# machin.net
KiCad netlist of a schematic drawn in Altium Designer
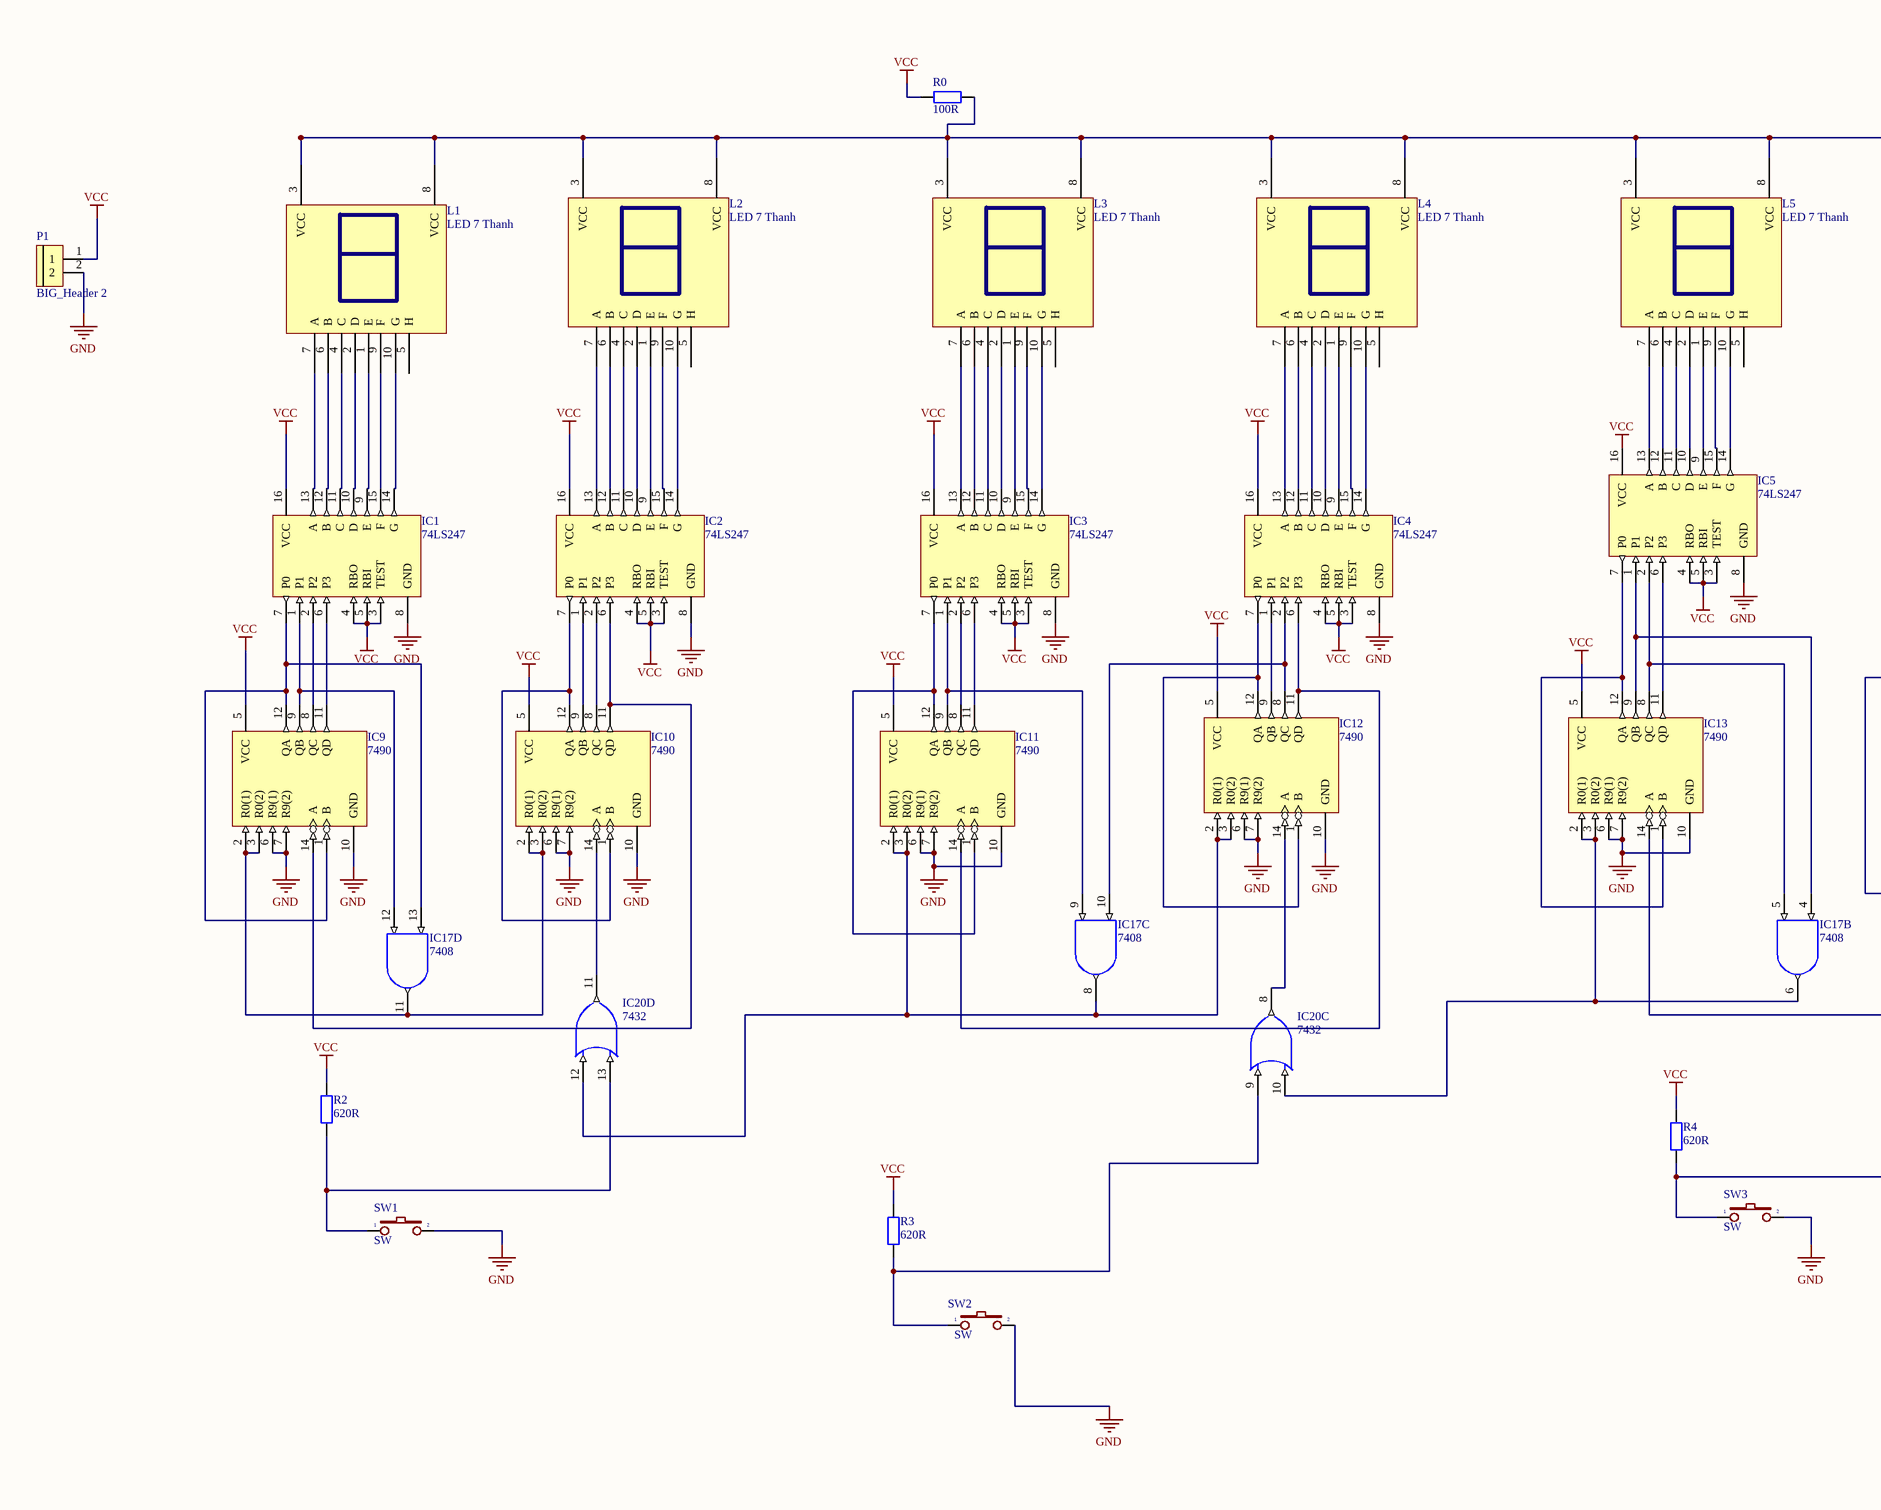
[diagram p0: machin.SchDoc, left]
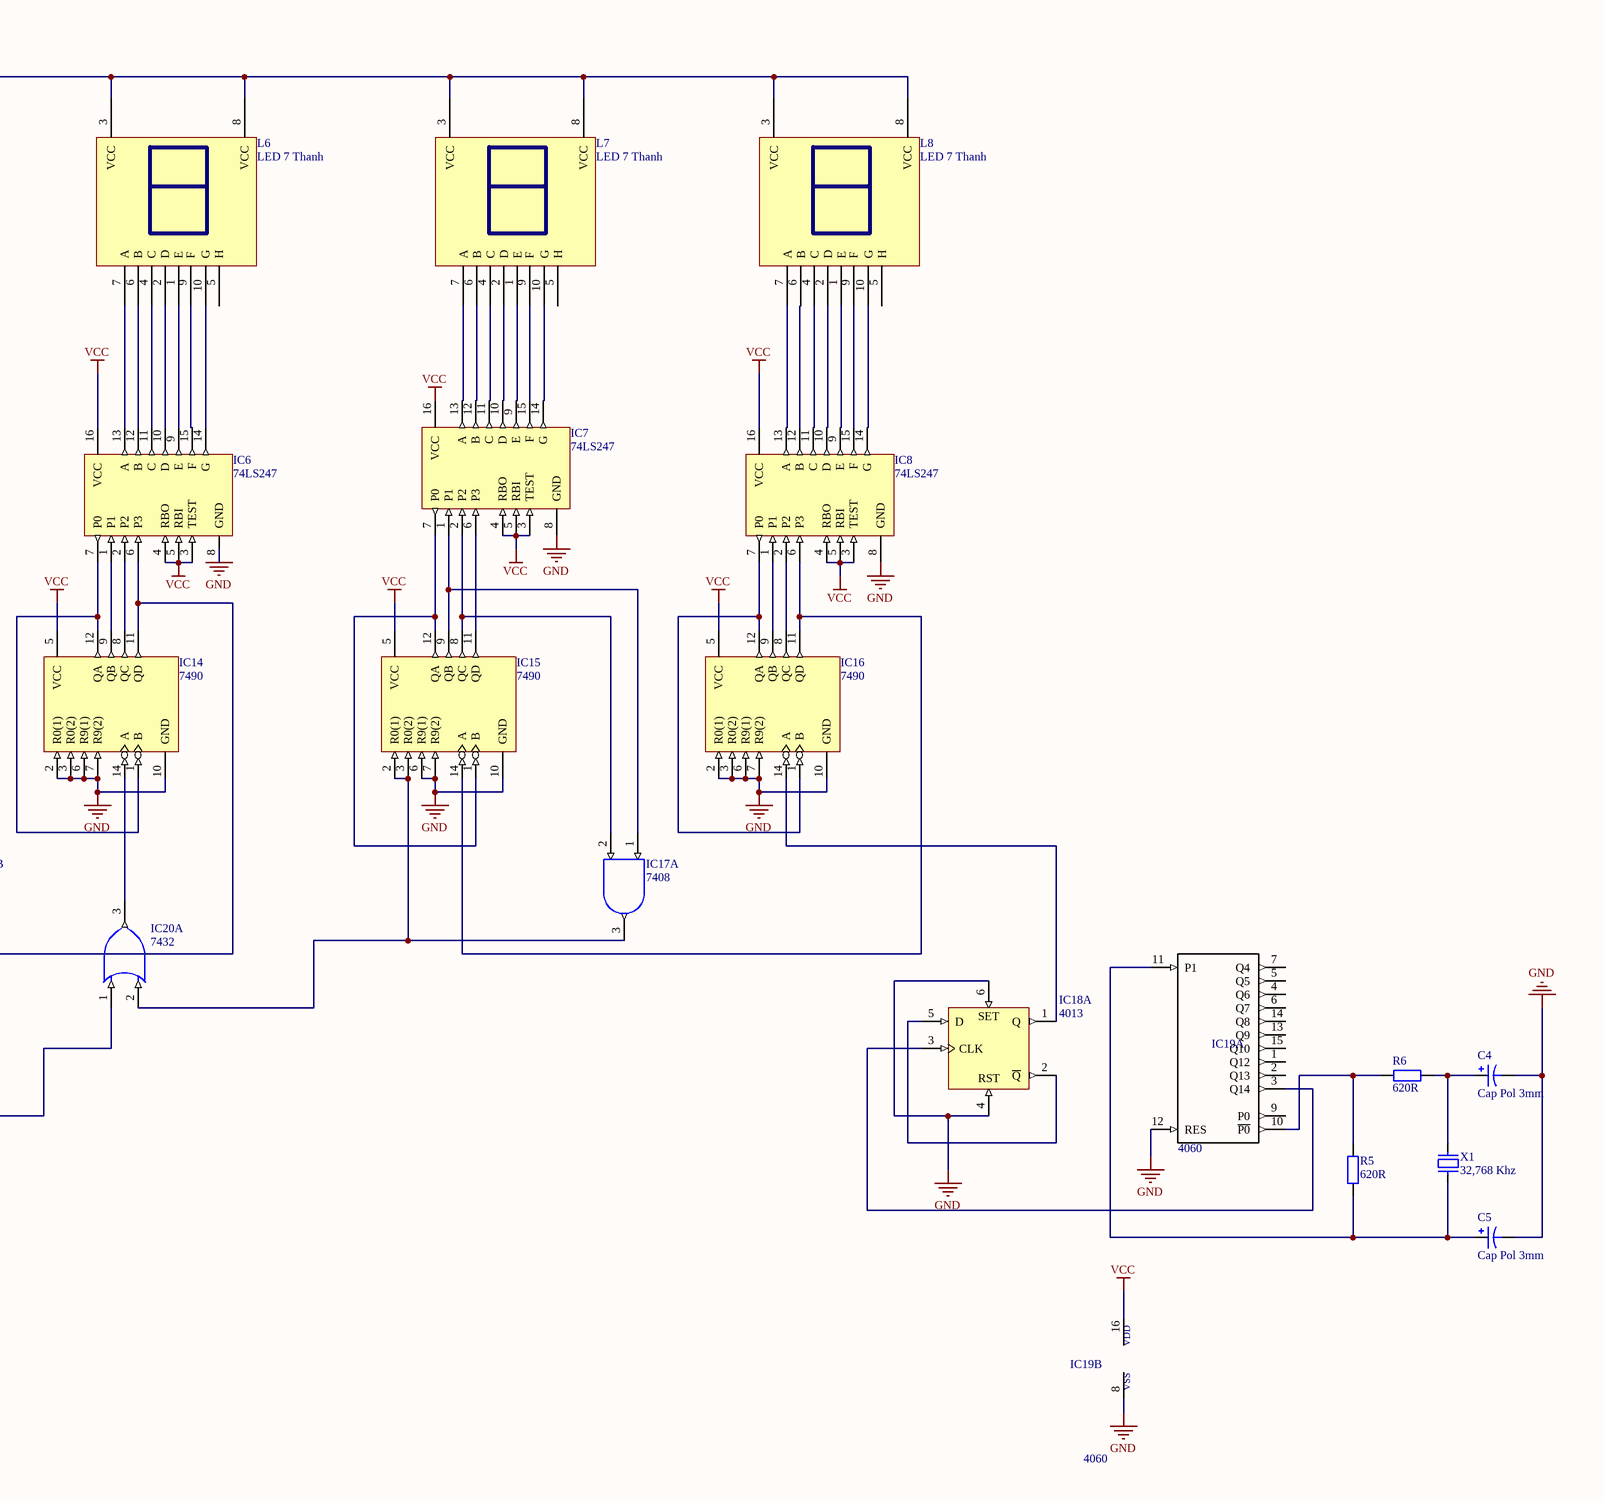
[diagram p1: machin.SchDoc, right]

(export (version "E")
  (design (tool "Eeschema 10.0.6"))
  (components
    (comp (ref "C4")
      (value "Cap Pol 3mm")
      (footprint "C3MM")
      (description "Polarized Capacitor (Axial)")
      (fields (field (name "PUBLISHER") "Altium Limited"))
      (libsource (lib "NBBLib 14-03-2012") (part "Cap Pol 3mm"))
    )
    (comp (ref "C5")
      (value "Cap Pol 3mm")
      (footprint "C3MM")
      (description "Polarized Capacitor (Axial)")
      (fields (field (name "PUBLISHER") "Altium Limited"))
      (libsource (lib "NBBLib 14-03-2012") (part "Cap Pol 3mm"))
    )
    (comp (ref "IC1")
      (value "74LS247")
      (footprint "DIP16")
      (fields (field (name "COPYRIGHT BY") "VanDungEvn@Gmail.com"))
      (libsource (lib "KhanhBK_SCH_Library_2") (part "74247"))
    )
    (comp (ref "IC2")
      (value "74LS247")
      (footprint "DIP16")
      (fields (field (name "COPYRIGHT BY") "VanDungEvn@Gmail.com"))
      (libsource (lib "KhanhBK_SCH_Library_2") (part "74247"))
    )
    (comp (ref "IC3")
      (value "74LS247")
      (footprint "DIP16")
      (fields (field (name "COPYRIGHT BY") "VanDungEvn@Gmail.com"))
      (libsource (lib "KhanhBK_SCH_Library_2") (part "74247"))
    )
    (comp (ref "IC4")
      (value "74LS247")
      (footprint "DIP16")
      (fields (field (name "COPYRIGHT BY") "VanDungEvn@Gmail.com"))
      (libsource (lib "KhanhBK_SCH_Library_2") (part "74247"))
    )
    (comp (ref "IC5")
      (value "74LS247")
      (footprint "DIP16")
      (fields (field (name "COPYRIGHT BY") "VanDungEvn@Gmail.com"))
      (libsource (lib "KhanhBK_SCH_Library_2") (part "74247"))
    )
    (comp (ref "IC6")
      (value "74LS247")
      (footprint "DIP16")
      (fields (field (name "COPYRIGHT BY") "VanDungEvn@Gmail.com"))
      (libsource (lib "KhanhBK_SCH_Library_2") (part "74247"))
    )
    (comp (ref "IC7")
      (value "74LS247")
      (footprint "DIP16")
      (fields (field (name "COPYRIGHT BY") "VanDungEvn@Gmail.com"))
      (libsource (lib "KhanhBK_SCH_Library_2") (part "74247"))
    )
    (comp (ref "IC8")
      (value "74LS247")
      (footprint "DIP16")
      (fields (field (name "COPYRIGHT BY") "VanDungEvn@Gmail.com"))
      (libsource (lib "KhanhBK_SCH_Library_2") (part "74247"))
    )
    (comp (ref "IC9")
      (value "7490")
      (footprint "DIP14/W0.3")
      (description "4-Bit Decade Counter")
      (libsource (lib "KhanhBK_SCH_Library_2") (part "7490"))
    )
    (comp (ref "IC10")
      (value "7490")
      (footprint "DIP14/W0.3")
      (description "4-Bit Decade Counter")
      (libsource (lib "KhanhBK_SCH_Library_2") (part "7490"))
    )
    (comp (ref "IC11")
      (value "7490")
      (footprint "DIP14/W0.3")
      (description "4-Bit Decade Counter")
      (libsource (lib "KhanhBK_SCH_Library_2") (part "7490"))
    )
    (comp (ref "IC12")
      (value "7490")
      (footprint "DIP14/W0.3")
      (description "4-Bit Decade Counter")
      (libsource (lib "KhanhBK_SCH_Library_2") (part "7490"))
    )
    (comp (ref "IC13")
      (value "7490")
      (footprint "DIP14/W0.3")
      (description "4-Bit Decade Counter")
      (libsource (lib "KhanhBK_SCH_Library_2") (part "7490"))
    )
    (comp (ref "IC14")
      (value "7490")
      (footprint "DIP14/W0.3")
      (description "4-Bit Decade Counter")
      (libsource (lib "KhanhBK_SCH_Library_2") (part "7490"))
    )
    (comp (ref "IC15")
      (value "7490")
      (footprint "DIP14/W0.3")
      (description "4-Bit Decade Counter")
      (libsource (lib "KhanhBK_SCH_Library_2") (part "7490"))
    )
    (comp (ref "IC16")
      (value "7490")
      (footprint "DIP14/W0.3")
      (description "4-Bit Decade Counter")
      (libsource (lib "KhanhBK_SCH_Library_2") (part "7490"))
    )
    (comp (ref "IC17")
      (value "7408")
      (footprint "DIP14/W0.3")
      (description "Quad 2-Input AND Gate")
      (libsource (lib "Library AL") (part "7408"))
    )
    (comp (ref "IC18")
      (value "4013")
      (footprint "DIP14")
      (description "Dual D-Type Flip-Flop")
      (fields (field (name "CREAT BY") "VanDungEvn@Gmail.com"))
      (libsource (lib "KhanhBK_SCH_Library_2") (part "4013"))
    )
    (comp (ref "IC19")
      (value "4060")
      (footprint "*DIL16")
      (description "Standoff; Round; Nylon; 6-32x3/8 Thread; 1/4 OD; 3/4 Length ¦ Abbatron / HH Smith 4060")
      (fields (field (name "MF") "Abbatron"))
      (libsource (lib "4060") (part "4060"))
    )
    (comp (ref "IC20")
      (value "7432")
      (footprint "DIP14/W0.3")
      (description "Quad 2-Input OR Gate")
      (libsource (lib "KhanhBK_SCH_Library_2") (part "7432"))
    )
    (comp (ref "L1")
      (value "LED 7 Thanh")
      (footprint "LED 7x1 0.56")
      (description "Dán")
      (libsource (lib "Led") (part "LED 7x1 0.56 Anot"))
    )
    (comp (ref "L2")
      (value "LED 7 Thanh")
      (footprint "LED 7x1 0.56")
      (description "Dán")
      (libsource (lib "Led") (part "LED 7x1 0.56 Anot"))
    )
    (comp (ref "L3")
      (value "LED 7 Thanh")
      (footprint "LED 7x1 0.56")
      (description "Dán")
      (libsource (lib "Led") (part "LED 7x1 0.56 Anot"))
    )
    (comp (ref "L4")
      (value "LED 7 Thanh")
      (footprint "LED 7x1 0.56")
      (description "Dán")
      (libsource (lib "Led") (part "LED 7x1 0.56 Anot"))
    )
    (comp (ref "L5")
      (value "LED 7 Thanh")
      (footprint "LED 7x1 0.56")
      (description "Dán")
      (libsource (lib "Led") (part "LED 7x1 0.56 Anot"))
    )
    (comp (ref "L6")
      (value "LED 7 Thanh")
      (footprint "LED 7x1 0.56")
      (description "Dán")
      (libsource (lib "Led") (part "LED 7x1 0.56 Anot"))
    )
    (comp (ref "L7")
      (value "LED 7 Thanh")
      (footprint "LED 7x1 0.56")
      (description "Dán")
      (libsource (lib "Led") (part "LED 7x1 0.56 Anot"))
    )
    (comp (ref "L8")
      (value "LED 7 Thanh")
      (footprint "LED 7x1 0.56")
      (description "Dán")
      (libsource (lib "Led") (part "LED 7x1 0.56 Anot"))
    )
    (comp (ref "P1")
      (value "BIG_Header 2")
      (footprint "BIG_Header 2")
      (libsource (lib "NBBLib 14-03-2012") (part "BIG_Header 2"))
    )
    (comp (ref "R0")
      (value "100R")
      (footprint "tro vach 1/2w")
      (description "Cắm")
      (libsource (lib "Resistor") (part "Tro Vach 1/2W 5% 100R"))
    )
    (comp (ref "R2")
      (value "620R")
      (footprint "tro vach 1/4w")
      (description "Cắm")
      (libsource (lib "Resistor") (part "Tro Vach 1/4W 5% 620R"))
    )
    (comp (ref "R3")
      (value "620R")
      (footprint "tro vach 1/4w")
      (description "Cắm")
      (libsource (lib "Resistor") (part "Tro Vach 1/4W 5% 620R"))
    )
    (comp (ref "R4")
      (value "620R")
      (footprint "tro vach 1/4w")
      (description "Cắm")
      (libsource (lib "Resistor") (part "Tro Vach 1/4W 5% 620R"))
    )
    (comp (ref "R5")
      (value "620R")
      (footprint "tro vach 1/4w")
      (description "Cắm")
      (libsource (lib "Resistor") (part "Tro Vach 1/4W 5% 620R"))
    )
    (comp (ref "R6")
      (value "620R")
      (footprint "tro vach 1/4w")
      (description "Cắm")
      (libsource (lib "Resistor") (part "Tro Vach 1/4W 5% 620R"))
    )
    (comp (ref "SW1")
      (value "SW")
      (footprint "SW2")
      (description "Switch button 2 pin")
      (libsource (lib "KhanhBK_SCH_Library_2") (part "SW2"))
    )
    (comp (ref "SW2")
      (value "SW")
      (footprint "SW2")
      (description "Switch button 2 pin")
      (libsource (lib "KhanhBK_SCH_Library_2") (part "SW2"))
    )
    (comp (ref "SW3")
      (value "SW")
      (footprint "SW2")
      (description "Switch button 2 pin")
      (libsource (lib "KhanhBK_SCH_Library_2") (part "SW2"))
    )
    (comp (ref "X1")
      (value "32,768 Khz")
      (footprint "XT32k")
      (description "Crystal 32,768kHz for timer real")
      (libsource (lib "KhanhBK_SCH_Library_2") (part "XT32k"))
    )
  )
  (nets
    (net (code "1") (name "GND") (class "Default")
      (node (ref "C4") (pin "2") (pinfunction "2_2") (pintype "passive"))
      (node (ref "C5") (pin "2") (pinfunction "2_2") (pintype "passive"))
      (node (ref "IC1") (pin "8") (pinfunction "GND_8") (pintype "power_in"))
      (node (ref "IC10") (pin "10") (pinfunction "GND_10") (pintype "power_in"))
      (node (ref "IC10") (pin "6") (pinfunction "R9(1)_6") (pintype "input"))
      (node (ref "IC10") (pin "7") (pinfunction "R9(2)_7") (pintype "input"))
      (node (ref "IC11") (pin "10") (pinfunction "GND_10") (pintype "power_in"))
      (node (ref "IC11") (pin "6") (pinfunction "R9(1)_6") (pintype "input"))
      (node (ref "IC11") (pin "7") (pinfunction "R9(2)_7") (pintype "input"))
      (node (ref "IC12") (pin "10") (pinfunction "GND_10") (pintype "power_in"))
      (node (ref "IC12") (pin "6") (pinfunction "R9(1)_6") (pintype "input"))
      (node (ref "IC12") (pin "7") (pinfunction "R9(2)_7") (pintype "input"))
      (node (ref "IC13") (pin "10") (pinfunction "GND_10") (pintype "power_in"))
      (node (ref "IC13") (pin "6") (pinfunction "R9(1)_6") (pintype "input"))
      (node (ref "IC13") (pin "7") (pinfunction "R9(2)_7") (pintype "input"))
      (node (ref "IC14") (pin "10") (pinfunction "GND_10") (pintype "power_in"))
      (node (ref "IC14") (pin "2") (pinfunction "R0(1)_2") (pintype "input"))
      (node (ref "IC14") (pin "3") (pinfunction "R0(2)_3") (pintype "input"))
      (node (ref "IC14") (pin "6") (pinfunction "R9(1)_6") (pintype "input"))
      (node (ref "IC14") (pin "7") (pinfunction "R9(2)_7") (pintype "input"))
      (node (ref "IC15") (pin "10") (pinfunction "GND_10") (pintype "power_in"))
      (node (ref "IC15") (pin "6") (pinfunction "R9(1)_6") (pintype "input"))
      (node (ref "IC15") (pin "7") (pinfunction "R9(2)_7") (pintype "input"))
      (node (ref "IC16") (pin "10") (pinfunction "GND_10") (pintype "power_in"))
      (node (ref "IC16") (pin "2") (pinfunction "R0(1)_2") (pintype "input"))
      (node (ref "IC16") (pin "3") (pinfunction "R0(2)_3") (pintype "input"))
      (node (ref "IC16") (pin "6") (pinfunction "R9(1)_6") (pintype "input"))
      (node (ref "IC16") (pin "7") (pinfunction "R9(2)_7") (pintype "input"))
      (node (ref "IC17") (pin "7") (pinfunction "GND_7") (pintype "power_in"))
      (node (ref "IC18") (pin "4") (pinfunction "RST_4") (pintype "input"))
      (node (ref "IC18") (pin "6") (pinfunction "S_6") (pintype "input"))
      (node (ref "IC18") (pin "7") (pinfunction "GND_7") (pintype "power_in"))
      (node (ref "IC19") (pin "12") (pinfunction "RES_12") (pintype "input"))
      (node (ref "IC19") (pin "8") (pinfunction "VSS_8") (pintype "power_in"))
      (node (ref "IC2") (pin "8") (pinfunction "GND_8") (pintype "power_in"))
      (node (ref "IC20") (pin "7") (pinfunction "GND_7") (pintype "power_in"))
      (node (ref "IC3") (pin "8") (pinfunction "GND_8") (pintype "power_in"))
      (node (ref "IC4") (pin "8") (pinfunction "GND_8") (pintype "power_in"))
      (node (ref "IC5") (pin "8") (pinfunction "GND_8") (pintype "power_in"))
      (node (ref "IC6") (pin "8") (pinfunction "GND_8") (pintype "power_in"))
      (node (ref "IC7") (pin "8") (pinfunction "GND_8") (pintype "power_in"))
      (node (ref "IC8") (pin "8") (pinfunction "GND_8") (pintype "power_in"))
      (node (ref "IC9") (pin "10") (pinfunction "GND_10") (pintype "power_in"))
      (node (ref "IC9") (pin "6") (pinfunction "R9(1)_6") (pintype "input"))
      (node (ref "IC9") (pin "7") (pinfunction "R9(2)_7") (pintype "input"))
      (node (ref "P1") (pin "2") (pinfunction "2_2") (pintype "passive"))
      (node (ref "SW1") (pin "2") (pinfunction "2_2") (pintype "passive"))
      (node (ref "SW2") (pin "2") (pinfunction "2_2") (pintype "passive"))
      (node (ref "SW3") (pin "2") (pinfunction "2_2") (pintype "passive"))
    )
    (net (code "2") (name "Net-(C4-Pad1)") (class "Default")
      (node (ref "C4") (pin "1") (pinfunction "1_1") (pintype "passive"))
      (node (ref "R6") (pin "1") (pinfunction "1_1") (pintype "passive"))
      (node (ref "X1") (pin "2") (pinfunction "2_2") (pintype "passive"))
    )
    (net (code "3") (name "Net-(IC1-A)") (class "Default")
      (node (ref "IC1") (pin "13") (pinfunction "A_13") (pintype "output"))
      (node (ref "L1") (pin "7") (pinfunction "A_7") (pintype "passive"))
    )
    (net (code "4") (name "Net-(IC1-B)") (class "Default")
      (node (ref "IC1") (pin "12") (pinfunction "B_12") (pintype "output"))
      (node (ref "L1") (pin "6") (pinfunction "B_6") (pintype "passive"))
    )
    (net (code "5") (name "Net-(IC1-C)") (class "Default")
      (node (ref "IC1") (pin "11") (pinfunction "C_11") (pintype "output"))
      (node (ref "L1") (pin "4") (pinfunction "C_4") (pintype "passive"))
    )
    (net (code "6") (name "Net-(IC1-D)") (class "Default")
      (node (ref "IC1") (pin "10") (pinfunction "D_10") (pintype "output"))
      (node (ref "L1") (pin "2") (pinfunction "D_2") (pintype "passive"))
    )
    (net (code "7") (name "Net-(IC1-E)") (class "Default")
      (node (ref "IC1") (pin "9") (pinfunction "E_9") (pintype "output"))
      (node (ref "L1") (pin "1") (pinfunction "E_1") (pintype "passive"))
    )
    (net (code "8") (name "Net-(IC1-F)") (class "Default")
      (node (ref "IC1") (pin "15") (pinfunction "F_15") (pintype "output"))
      (node (ref "L1") (pin "9") (pinfunction "F_9") (pintype "passive"))
    )
    (net (code "9") (name "Net-(IC1-G)") (class "Default")
      (node (ref "IC1") (pin "14") (pinfunction "G_14") (pintype "output"))
      (node (ref "L1") (pin "10") (pinfunction "G_10") (pintype "passive"))
    )
    (net (code "10") (name "Net-(IC1-P0)") (class "Default")
      (node (ref "IC1") (pin "7") (pinfunction "P0_7") (pintype "output"))
      (node (ref "IC17") (pin "13") (pinfunction "A_13") (pintype "input"))
      (node (ref "IC9") (pin "1") (pinfunction "B_1") (pintype "input"))
      (node (ref "IC9") (pin "12") (pinfunction "QA_12") (pintype "output"))
    )
    (net (code "11") (name "Net-(IC1-P1)") (class "Default")
      (node (ref "IC1") (pin "1") (pinfunction "P1_1") (pintype "input"))
      (node (ref "IC17") (pin "12") (pinfunction "B_12") (pintype "input"))
      (node (ref "IC9") (pin "9") (pinfunction "QB_9") (pintype "output"))
    )
    (net (code "12") (name "Net-(IC1-P2)") (class "Default")
      (node (ref "IC1") (pin "2") (pinfunction "P2_2") (pintype "input"))
      (node (ref "IC9") (pin "8") (pinfunction "QC_8") (pintype "output"))
    )
    (net (code "13") (name "Net-(IC1-P3)") (class "Default")
      (node (ref "IC1") (pin "6") (pinfunction "P3_6") (pintype "input"))
      (node (ref "IC9") (pin "11") (pinfunction "QD_11") (pintype "output"))
    )
    (net (code "14") (name "Net-(IC2-A)") (class "Default")
      (node (ref "IC2") (pin "13") (pinfunction "A_13") (pintype "output"))
      (node (ref "L2") (pin "7") (pinfunction "A_7") (pintype "passive"))
    )
    (net (code "15") (name "Net-(IC2-B)") (class "Default")
      (node (ref "IC2") (pin "12") (pinfunction "B_12") (pintype "output"))
      (node (ref "L2") (pin "6") (pinfunction "B_6") (pintype "passive"))
    )
    (net (code "16") (name "Net-(IC2-C)") (class "Default")
      (node (ref "IC2") (pin "11") (pinfunction "C_11") (pintype "output"))
      (node (ref "L2") (pin "4") (pinfunction "C_4") (pintype "passive"))
    )
    (net (code "17") (name "Net-(IC2-D)") (class "Default")
      (node (ref "IC2") (pin "10") (pinfunction "D_10") (pintype "output"))
      (node (ref "L2") (pin "2") (pinfunction "D_2") (pintype "passive"))
    )
    (net (code "18") (name "Net-(IC2-E)") (class "Default")
      (node (ref "IC2") (pin "9") (pinfunction "E_9") (pintype "output"))
      (node (ref "L2") (pin "1") (pinfunction "E_1") (pintype "passive"))
    )
    (net (code "19") (name "Net-(IC2-F)") (class "Default")
      (node (ref "IC2") (pin "15") (pinfunction "F_15") (pintype "output"))
      (node (ref "L2") (pin "9") (pinfunction "F_9") (pintype "passive"))
    )
    (net (code "20") (name "Net-(IC2-G)") (class "Default")
      (node (ref "IC2") (pin "14") (pinfunction "G_14") (pintype "output"))
      (node (ref "L2") (pin "10") (pinfunction "G_10") (pintype "passive"))
    )
    (net (code "21") (name "Net-(IC3-A)") (class "Default")
      (node (ref "IC3") (pin "13") (pinfunction "A_13") (pintype "output"))
      (node (ref "L3") (pin "7") (pinfunction "A_7") (pintype "passive"))
    )
    (net (code "22") (name "Net-(IC3-B)") (class "Default")
      (node (ref "IC3") (pin "12") (pinfunction "B_12") (pintype "output"))
      (node (ref "L3") (pin "6") (pinfunction "B_6") (pintype "passive"))
    )
    (net (code "23") (name "Net-(IC3-C)") (class "Default")
      (node (ref "IC3") (pin "11") (pinfunction "C_11") (pintype "output"))
      (node (ref "L3") (pin "4") (pinfunction "C_4") (pintype "passive"))
    )
    (net (code "24") (name "Net-(IC3-D)") (class "Default")
      (node (ref "IC3") (pin "10") (pinfunction "D_10") (pintype "output"))
      (node (ref "L3") (pin "2") (pinfunction "D_2") (pintype "passive"))
    )
    (net (code "25") (name "Net-(IC3-E)") (class "Default")
      (node (ref "IC3") (pin "9") (pinfunction "E_9") (pintype "output"))
      (node (ref "L3") (pin "1") (pinfunction "E_1") (pintype "passive"))
    )
    (net (code "26") (name "Net-(IC3-F)") (class "Default")
      (node (ref "IC3") (pin "15") (pinfunction "F_15") (pintype "output"))
      (node (ref "L3") (pin "9") (pinfunction "F_9") (pintype "passive"))
    )
    (net (code "27") (name "Net-(IC3-G)") (class "Default")
      (node (ref "IC3") (pin "14") (pinfunction "G_14") (pintype "output"))
      (node (ref "L3") (pin "10") (pinfunction "G_10") (pintype "passive"))
    )
    (net (code "28") (name "Net-(IC4-A)") (class "Default")
      (node (ref "IC4") (pin "13") (pinfunction "A_13") (pintype "output"))
      (node (ref "L4") (pin "7") (pinfunction "A_7") (pintype "passive"))
    )
    (net (code "29") (name "Net-(IC4-B)") (class "Default")
      (node (ref "IC4") (pin "12") (pinfunction "B_12") (pintype "output"))
      (node (ref "L4") (pin "6") (pinfunction "B_6") (pintype "passive"))
    )
    (net (code "30") (name "Net-(IC4-C)") (class "Default")
      (node (ref "IC4") (pin "11") (pinfunction "C_11") (pintype "output"))
      (node (ref "L4") (pin "4") (pinfunction "C_4") (pintype "passive"))
    )
    (net (code "31") (name "Net-(IC4-D)") (class "Default")
      (node (ref "IC4") (pin "10") (pinfunction "D_10") (pintype "output"))
      (node (ref "L4") (pin "2") (pinfunction "D_2") (pintype "passive"))
    )
    (net (code "32") (name "Net-(IC4-E)") (class "Default")
      (node (ref "IC4") (pin "9") (pinfunction "E_9") (pintype "output"))
      (node (ref "L4") (pin "1") (pinfunction "E_1") (pintype "passive"))
    )
    (net (code "33") (name "Net-(IC4-F)") (class "Default")
      (node (ref "IC4") (pin "15") (pinfunction "F_15") (pintype "output"))
      (node (ref "L4") (pin "9") (pinfunction "F_9") (pintype "passive"))
    )
    (net (code "34") (name "Net-(IC4-G)") (class "Default")
      (node (ref "IC4") (pin "14") (pinfunction "G_14") (pintype "output"))
      (node (ref "L4") (pin "10") (pinfunction "G_10") (pintype "passive"))
    )
    (net (code "35") (name "Net-(IC5-A)") (class "Default")
      (node (ref "IC5") (pin "13") (pinfunction "A_13") (pintype "output"))
      (node (ref "L5") (pin "7") (pinfunction "A_7") (pintype "passive"))
    )
    (net (code "36") (name "Net-(IC5-B)") (class "Default")
      (node (ref "IC5") (pin "12") (pinfunction "B_12") (pintype "output"))
      (node (ref "L5") (pin "6") (pinfunction "B_6") (pintype "passive"))
    )
    (net (code "37") (name "Net-(IC5-C)") (class "Default")
      (node (ref "IC5") (pin "11") (pinfunction "C_11") (pintype "output"))
      (node (ref "L5") (pin "4") (pinfunction "C_4") (pintype "passive"))
    )
    (net (code "38") (name "Net-(IC5-D)") (class "Default")
      (node (ref "IC5") (pin "10") (pinfunction "D_10") (pintype "output"))
      (node (ref "L5") (pin "2") (pinfunction "D_2") (pintype "passive"))
    )
    (net (code "39") (name "Net-(IC5-E)") (class "Default")
      (node (ref "IC5") (pin "9") (pinfunction "E_9") (pintype "output"))
      (node (ref "L5") (pin "1") (pinfunction "E_1") (pintype "passive"))
    )
    (net (code "40") (name "Net-(IC5-F)") (class "Default")
      (node (ref "IC5") (pin "15") (pinfunction "F_15") (pintype "output"))
      (node (ref "L5") (pin "9") (pinfunction "F_9") (pintype "passive"))
    )
    (net (code "41") (name "Net-(IC5-G)") (class "Default")
      (node (ref "IC5") (pin "14") (pinfunction "G_14") (pintype "output"))
      (node (ref "L5") (pin "10") (pinfunction "G_10") (pintype "passive"))
    )
    (net (code "42") (name "Net-(IC6-A)") (class "Default")
      (node (ref "IC6") (pin "13") (pinfunction "A_13") (pintype "output"))
      (node (ref "L6") (pin "7") (pinfunction "A_7") (pintype "passive"))
    )
    (net (code "43") (name "Net-(IC6-B)") (class "Default")
      (node (ref "IC6") (pin "12") (pinfunction "B_12") (pintype "output"))
      (node (ref "L6") (pin "6") (pinfunction "B_6") (pintype "passive"))
    )
    (net (code "44") (name "Net-(IC6-C)") (class "Default")
      (node (ref "IC6") (pin "11") (pinfunction "C_11") (pintype "output"))
      (node (ref "L6") (pin "4") (pinfunction "C_4") (pintype "passive"))
    )
    (net (code "45") (name "Net-(IC6-D)") (class "Default")
      (node (ref "IC6") (pin "10") (pinfunction "D_10") (pintype "output"))
      (node (ref "L6") (pin "2") (pinfunction "D_2") (pintype "passive"))
    )
    (net (code "46") (name "Net-(IC6-E)") (class "Default")
      (node (ref "IC6") (pin "9") (pinfunction "E_9") (pintype "output"))
      (node (ref "L6") (pin "1") (pinfunction "E_1") (pintype "passive"))
    )
    (net (code "47") (name "Net-(IC6-F)") (class "Default")
      (node (ref "IC6") (pin "15") (pinfunction "F_15") (pintype "output"))
      (node (ref "L6") (pin "9") (pinfunction "F_9") (pintype "passive"))
    )
    (net (code "48") (name "Net-(IC6-G)") (class "Default")
      (node (ref "IC6") (pin "14") (pinfunction "G_14") (pintype "output"))
      (node (ref "L6") (pin "10") (pinfunction "G_10") (pintype "passive"))
    )
    (net (code "49") (name "Net-(IC7-A)") (class "Default")
      (node (ref "IC7") (pin "13") (pinfunction "A_13") (pintype "output"))
      (node (ref "L7") (pin "7") (pinfunction "A_7") (pintype "passive"))
    )
    (net (code "50") (name "Net-(IC7-B)") (class "Default")
      (node (ref "IC7") (pin "12") (pinfunction "B_12") (pintype "output"))
      (node (ref "L7") (pin "6") (pinfunction "B_6") (pintype "passive"))
    )
    (net (code "51") (name "Net-(IC7-C)") (class "Default")
      (node (ref "IC7") (pin "11") (pinfunction "C_11") (pintype "output"))
      (node (ref "L7") (pin "4") (pinfunction "C_4") (pintype "passive"))
    )
    (net (code "52") (name "Net-(IC7-D)") (class "Default")
      (node (ref "IC7") (pin "10") (pinfunction "D_10") (pintype "output"))
      (node (ref "L7") (pin "2") (pinfunction "D_2") (pintype "passive"))
    )
    (net (code "53") (name "Net-(IC7-E)") (class "Default")
      (node (ref "IC7") (pin "9") (pinfunction "E_9") (pintype "output"))
      (node (ref "L7") (pin "1") (pinfunction "E_1") (pintype "passive"))
    )
    (net (code "54") (name "Net-(IC7-F)") (class "Default")
      (node (ref "IC7") (pin "15") (pinfunction "F_15") (pintype "output"))
      (node (ref "L7") (pin "9") (pinfunction "F_9") (pintype "passive"))
    )
    (net (code "55") (name "Net-(IC7-G)") (class "Default")
      (node (ref "IC7") (pin "14") (pinfunction "G_14") (pintype "output"))
      (node (ref "L7") (pin "10") (pinfunction "G_10") (pintype "passive"))
    )
    (net (code "56") (name "Net-(IC8-A)") (class "Default")
      (node (ref "IC8") (pin "13") (pinfunction "A_13") (pintype "output"))
      (node (ref "L8") (pin "7") (pinfunction "A_7") (pintype "passive"))
    )
    (net (code "57") (name "Net-(IC8-B)") (class "Default")
      (node (ref "IC8") (pin "12") (pinfunction "B_12") (pintype "output"))
      (node (ref "L8") (pin "6") (pinfunction "B_6") (pintype "passive"))
    )
    (net (code "58") (name "Net-(IC8-C)") (class "Default")
      (node (ref "IC8") (pin "11") (pinfunction "C_11") (pintype "output"))
      (node (ref "L8") (pin "4") (pinfunction "C_4") (pintype "passive"))
    )
    (net (code "59") (name "Net-(IC8-D)") (class "Default")
      (node (ref "IC8") (pin "10") (pinfunction "D_10") (pintype "output"))
      (node (ref "L8") (pin "2") (pinfunction "D_2") (pintype "passive"))
    )
    (net (code "60") (name "Net-(IC8-E)") (class "Default")
      (node (ref "IC8") (pin "9") (pinfunction "E_9") (pintype "output"))
      (node (ref "L8") (pin "1") (pinfunction "E_1") (pintype "passive"))
    )
    (net (code "61") (name "Net-(IC8-F)") (class "Default")
      (node (ref "IC8") (pin "15") (pinfunction "F_15") (pintype "output"))
      (node (ref "L8") (pin "9") (pinfunction "F_9") (pintype "passive"))
    )
    (net (code "62") (name "Net-(IC8-G)") (class "Default")
      (node (ref "IC8") (pin "14") (pinfunction "G_14") (pintype "output"))
      (node (ref "L8") (pin "10") (pinfunction "G_10") (pintype "passive"))
    )
    (net (code "63") (name "Net-(IC10-A)") (class "Default")
      (node (ref "IC10") (pin "14") (pinfunction "A_14") (pintype "input"))
      (node (ref "IC20") (pin "11") (pinfunction "Y_11") (pintype "output"))
    )
    (net (code "64") (name "Net-(IC10-B)") (class "Default")
      (node (ref "IC10") (pin "1") (pinfunction "B_1") (pintype "input"))
      (node (ref "IC10") (pin "12") (pinfunction "QA_12") (pintype "output"))
      (node (ref "IC2") (pin "7") (pinfunction "P0_7") (pintype "output"))
    )
    (net (code "65") (name "Net-(IC10-QB)") (class "Default")
      (node (ref "IC10") (pin "9") (pinfunction "QB_9") (pintype "output"))
      (node (ref "IC2") (pin "1") (pinfunction "P1_1") (pintype "input"))
    )
    (net (code "66") (name "Net-(IC10-QC)") (class "Default")
      (node (ref "IC10") (pin "8") (pinfunction "QC_8") (pintype "output"))
      (node (ref "IC2") (pin "2") (pinfunction "P2_2") (pintype "input"))
    )
    (net (code "67") (name "Net-(IC10-QD)") (class "Default")
      (node (ref "IC10") (pin "11") (pinfunction "QD_11") (pintype "output"))
      (node (ref "IC2") (pin "6") (pinfunction "P3_6") (pintype "input"))
      (node (ref "IC9") (pin "14") (pinfunction "A_14") (pintype "input"))
    )
    (net (code "68") (name "Net-(IC10-R0(1))") (class "Default")
      (node (ref "IC10") (pin "2") (pinfunction "R0(1)_2") (pintype "input"))
      (node (ref "IC10") (pin "3") (pinfunction "R0(2)_3") (pintype "input"))
      (node (ref "IC17") (pin "11") (pinfunction "O_11") (pintype "output"))
      (node (ref "IC9") (pin "2") (pinfunction "R0(1)_2") (pintype "input"))
      (node (ref "IC9") (pin "3") (pinfunction "R0(2)_3") (pintype "input"))
    )
    (net (code "69") (name "Net-(IC11-A)") (class "Default")
      (node (ref "IC11") (pin "14") (pinfunction "A_14") (pintype "input"))
      (node (ref "IC12") (pin "11") (pinfunction "QD_11") (pintype "output"))
      (node (ref "IC4") (pin "6") (pinfunction "P3_6") (pintype "input"))
    )
    (net (code "70") (name "Net-(IC11-B)") (class "Default")
      (node (ref "IC11") (pin "1") (pinfunction "B_1") (pintype "input"))
      (node (ref "IC11") (pin "12") (pinfunction "QA_12") (pintype "output"))
      (node (ref "IC3") (pin "7") (pinfunction "P0_7") (pintype "output"))
    )
    (net (code "71") (name "Net-(IC11-QB)") (class "Default")
      (node (ref "IC11") (pin "9") (pinfunction "QB_9") (pintype "output"))
      (node (ref "IC17") (pin "9") (pinfunction "B_9") (pintype "input"))
      (node (ref "IC3") (pin "1") (pinfunction "P1_1") (pintype "input"))
    )
    (net (code "72") (name "Net-(IC11-QC)") (class "Default")
      (node (ref "IC11") (pin "8") (pinfunction "QC_8") (pintype "output"))
      (node (ref "IC3") (pin "2") (pinfunction "P2_2") (pintype "input"))
    )
    (net (code "73") (name "Net-(IC11-QD)") (class "Default")
      (node (ref "IC11") (pin "11") (pinfunction "QD_11") (pintype "output"))
      (node (ref "IC3") (pin "6") (pinfunction "P3_6") (pintype "input"))
    )
    (net (code "74") (name "Net-(IC11-R0(1))") (class "Default")
      (node (ref "IC11") (pin "2") (pinfunction "R0(1)_2") (pintype "input"))
      (node (ref "IC11") (pin "3") (pinfunction "R0(2)_3") (pintype "input"))
      (node (ref "IC12") (pin "2") (pinfunction "R0(1)_2") (pintype "input"))
      (node (ref "IC12") (pin "3") (pinfunction "R0(2)_3") (pintype "input"))
      (node (ref "IC17") (pin "8") (pinfunction "O_8") (pintype "output"))
      (node (ref "IC20") (pin "12") (pinfunction "A_12") (pintype "input"))
    )
    (net (code "75") (name "Net-(IC12-A)") (class "Default")
      (node (ref "IC12") (pin "14") (pinfunction "A_14") (pintype "input"))
      (node (ref "IC20") (pin "8") (pinfunction "Y_8") (pintype "output"))
    )
    (net (code "76") (name "Net-(IC12-B)") (class "Default")
      (node (ref "IC12") (pin "1") (pinfunction "B_1") (pintype "input"))
      (node (ref "IC12") (pin "12") (pinfunction "QA_12") (pintype "output"))
      (node (ref "IC4") (pin "7") (pinfunction "P0_7") (pintype "output"))
    )
    (net (code "77") (name "Net-(IC12-QB)") (class "Default")
      (node (ref "IC12") (pin "9") (pinfunction "QB_9") (pintype "output"))
      (node (ref "IC4") (pin "1") (pinfunction "P1_1") (pintype "input"))
    )
    (net (code "78") (name "Net-(IC12-QC)") (class "Default")
      (node (ref "IC12") (pin "8") (pinfunction "QC_8") (pintype "output"))
      (node (ref "IC17") (pin "10") (pinfunction "A_10") (pintype "input"))
      (node (ref "IC4") (pin "2") (pinfunction "P2_2") (pintype "input"))
    )
    (net (code "79") (name "Net-(IC13-A)") (class "Default")
      (node (ref "IC13") (pin "14") (pinfunction "A_14") (pintype "input"))
      (node (ref "IC14") (pin "11") (pinfunction "QD_11") (pintype "output"))
      (node (ref "IC6") (pin "6") (pinfunction "P3_6") (pintype "input"))
    )
    (net (code "80") (name "Net-(IC13-B)") (class "Default")
      (node (ref "IC13") (pin "1") (pinfunction "B_1") (pintype "input"))
      (node (ref "IC13") (pin "12") (pinfunction "QA_12") (pintype "output"))
      (node (ref "IC5") (pin "7") (pinfunction "P0_7") (pintype "output"))
    )
    (net (code "81") (name "Net-(IC13-QB)") (class "Default")
      (node (ref "IC13") (pin "9") (pinfunction "QB_9") (pintype "output"))
      (node (ref "IC17") (pin "4") (pinfunction "A_4") (pintype "input"))
      (node (ref "IC5") (pin "1") (pinfunction "P1_1") (pintype "input"))
    )
    (net (code "82") (name "Net-(IC13-QC)") (class "Default")
      (node (ref "IC13") (pin "8") (pinfunction "QC_8") (pintype "output"))
      (node (ref "IC17") (pin "5") (pinfunction "B_5") (pintype "input"))
      (node (ref "IC5") (pin "2") (pinfunction "P2_2") (pintype "input"))
    )
    (net (code "83") (name "Net-(IC13-QD)") (class "Default")
      (node (ref "IC13") (pin "11") (pinfunction "QD_11") (pintype "output"))
      (node (ref "IC5") (pin "6") (pinfunction "P3_6") (pintype "input"))
    )
    (net (code "84") (name "Net-(IC13-R0(1))") (class "Default")
      (node (ref "IC13") (pin "2") (pinfunction "R0(1)_2") (pintype "input"))
      (node (ref "IC13") (pin "3") (pinfunction "R0(2)_3") (pintype "input"))
      (node (ref "IC17") (pin "6") (pinfunction "O_6") (pintype "output"))
      (node (ref "IC20") (pin "10") (pinfunction "B_10") (pintype "input"))
    )
    (net (code "85") (name "Net-(IC14-A)") (class "Default")
      (node (ref "IC14") (pin "14") (pinfunction "A_14") (pintype "input"))
      (node (ref "IC20") (pin "3") (pinfunction "Y_3") (pintype "output"))
    )
    (net (code "86") (name "Net-(IC14-B)") (class "Default")
      (node (ref "IC14") (pin "1") (pinfunction "B_1") (pintype "input"))
      (node (ref "IC14") (pin "12") (pinfunction "QA_12") (pintype "output"))
      (node (ref "IC6") (pin "7") (pinfunction "P0_7") (pintype "output"))
    )
    (net (code "87") (name "Net-(IC14-QB)") (class "Default")
      (node (ref "IC14") (pin "9") (pinfunction "QB_9") (pintype "output"))
      (node (ref "IC6") (pin "1") (pinfunction "P1_1") (pintype "input"))
    )
    (net (code "88") (name "Net-(IC14-QC)") (class "Default")
      (node (ref "IC14") (pin "8") (pinfunction "QC_8") (pintype "output"))
      (node (ref "IC6") (pin "2") (pinfunction "P2_2") (pintype "input"))
    )
    (net (code "89") (name "Net-(IC15-A)") (class "Default")
      (node (ref "IC15") (pin "14") (pinfunction "A_14") (pintype "input"))
      (node (ref "IC16") (pin "11") (pinfunction "QD_11") (pintype "output"))
      (node (ref "IC8") (pin "6") (pinfunction "P3_6") (pintype "input"))
    )
    (net (code "90") (name "Net-(IC15-B)") (class "Default")
      (node (ref "IC15") (pin "1") (pinfunction "B_1") (pintype "input"))
      (node (ref "IC15") (pin "12") (pinfunction "QA_12") (pintype "output"))
      (node (ref "IC7") (pin "7") (pinfunction "P0_7") (pintype "output"))
    )
    (net (code "91") (name "Net-(IC15-QB)") (class "Default")
      (node (ref "IC15") (pin "9") (pinfunction "QB_9") (pintype "output"))
      (node (ref "IC17") (pin "1") (pinfunction "A_1") (pintype "input"))
      (node (ref "IC7") (pin "1") (pinfunction "P1_1") (pintype "input"))
    )
    (net (code "92") (name "Net-(IC15-QC)") (class "Default")
      (node (ref "IC15") (pin "8") (pinfunction "QC_8") (pintype "output"))
      (node (ref "IC17") (pin "2") (pinfunction "B_2") (pintype "input"))
      (node (ref "IC7") (pin "2") (pinfunction "P2_2") (pintype "input"))
    )
    (net (code "93") (name "Net-(IC15-QD)") (class "Default")
      (node (ref "IC15") (pin "11") (pinfunction "QD_11") (pintype "output"))
      (node (ref "IC7") (pin "6") (pinfunction "P3_6") (pintype "input"))
    )
    (net (code "94") (name "Net-(IC15-R0(1))") (class "Default")
      (node (ref "IC15") (pin "2") (pinfunction "R0(1)_2") (pintype "input"))
      (node (ref "IC15") (pin "3") (pinfunction "R0(2)_3") (pintype "input"))
      (node (ref "IC17") (pin "3") (pinfunction "O_3") (pintype "output"))
      (node (ref "IC20") (pin "2") (pinfunction "B_2") (pintype "input"))
    )
    (net (code "95") (name "Net-(IC16-A)") (class "Default")
      (node (ref "IC16") (pin "14") (pinfunction "A_14") (pintype "input"))
      (node (ref "IC18") (pin "1") (pinfunction "Q_1") (pintype "output"))
    )
    (net (code "96") (name "Net-(IC16-B)") (class "Default")
      (node (ref "IC16") (pin "1") (pinfunction "B_1") (pintype "input"))
      (node (ref "IC16") (pin "12") (pinfunction "QA_12") (pintype "output"))
      (node (ref "IC8") (pin "7") (pinfunction "P0_7") (pintype "output"))
    )
    (net (code "97") (name "Net-(IC16-QB)") (class "Default")
      (node (ref "IC16") (pin "9") (pinfunction "QB_9") (pintype "output"))
      (node (ref "IC8") (pin "1") (pinfunction "P1_1") (pintype "input"))
    )
    (net (code "98") (name "Net-(IC16-QC)") (class "Default")
      (node (ref "IC16") (pin "8") (pinfunction "QC_8") (pintype "output"))
      (node (ref "IC8") (pin "2") (pinfunction "P2_2") (pintype "input"))
    )
    (net (code "99") (name "Net-(IC18A-CLK)") (class "Default")
      (node (ref "IC18") (pin "3") (pinfunction "CLK_3") (pintype "input"))
      (node (ref "IC19") (pin "3") (pinfunction "Q14_3") (pintype "output"))
    )
    (net (code "100") (name "Net-(IC18A-D)") (class "Default")
      (node (ref "IC18") (pin "2") (pinfunction "~{Q}_2") (pintype "output"))
      (node (ref "IC18") (pin "5") (pinfunction "D_5") (pintype "input"))
    )
    (net (code "101") (name "Net-(IC19A-P1)") (class "Default")
      (node (ref "C5") (pin "1") (pinfunction "1_1") (pintype "passive"))
      (node (ref "IC19") (pin "11") (pinfunction "P1_11") (pintype "input"))
      (node (ref "R5") (pin "1") (pinfunction "1_1") (pintype "passive"))
      (node (ref "X1") (pin "1") (pinfunction "1_1") (pintype "passive"))
    )
    (net (code "102") (name "Net-(IC19A-~{P0})") (class "Default")
      (node (ref "IC19") (pin "10") (pinfunction "~{P0}_10") (pintype "output"))
      (node (ref "R5") (pin "2") (pinfunction "2_2") (pintype "passive"))
      (node (ref "R6") (pin "2") (pinfunction "2_2") (pintype "passive"))
    )
    (net (code "103") (name "Net-(IC20A-A)") (class "Default")
      (node (ref "IC20") (pin "1") (pinfunction "A_1") (pintype "input"))
      (node (ref "R4") (pin "1") (pinfunction "1_1") (pintype "passive"))
      (node (ref "SW3") (pin "1") (pinfunction "1_1") (pintype "passive"))
    )
    (net (code "104") (name "Net-(IC20C-A)") (class "Default")
      (node (ref "IC20") (pin "9") (pinfunction "A_9") (pintype "input"))
      (node (ref "R3") (pin "1") (pinfunction "1_1") (pintype "passive"))
      (node (ref "SW2") (pin "1") (pinfunction "1_1") (pintype "passive"))
    )
    (net (code "105") (name "Net-(IC20D-B)") (class "Default")
      (node (ref "IC20") (pin "13") (pinfunction "B_13") (pintype "input"))
      (node (ref "R2") (pin "1") (pinfunction "1_1") (pintype "passive"))
      (node (ref "SW1") (pin "1") (pinfunction "1_1") (pintype "passive"))
    )
    (net (code "106") (name "Net-(L1-VCC-Pad3)") (class "Default")
      (node (ref "L1") (pin "3") (pinfunction "VCC_3") (pintype "passive"))
      (node (ref "L1") (pin "8") (pinfunction "VCC_8") (pintype "passive"))
      (node (ref "L2") (pin "3") (pinfunction "VCC_3") (pintype "passive"))
      (node (ref "L2") (pin "8") (pinfunction "VCC_8") (pintype "passive"))
      (node (ref "L3") (pin "3") (pinfunction "VCC_3") (pintype "passive"))
      (node (ref "L3") (pin "8") (pinfunction "VCC_8") (pintype "passive"))
      (node (ref "L4") (pin "3") (pinfunction "VCC_3") (pintype "passive"))
      (node (ref "L4") (pin "8") (pinfunction "VCC_8") (pintype "passive"))
      (node (ref "L5") (pin "3") (pinfunction "VCC_3") (pintype "passive"))
      (node (ref "L5") (pin "8") (pinfunction "VCC_8") (pintype "passive"))
      (node (ref "L6") (pin "3") (pinfunction "VCC_3") (pintype "passive"))
      (node (ref "L6") (pin "8") (pinfunction "VCC_8") (pintype "passive"))
      (node (ref "L7") (pin "3") (pinfunction "VCC_3") (pintype "passive"))
      (node (ref "L7") (pin "8") (pinfunction "VCC_8") (pintype "passive"))
      (node (ref "L8") (pin "3") (pinfunction "VCC_3") (pintype "passive"))
      (node (ref "L8") (pin "8") (pinfunction "VCC_8") (pintype "passive"))
      (node (ref "R0") (pin "2") (pinfunction "2_2") (pintype "passive"))
    )
    (net (code "107") (name "VCC") (class "Default")
      (node (ref "IC1") (pin "16") (pinfunction "VCC_16") (pintype "power_in"))
      (node (ref "IC1") (pin "3") (pinfunction "TEST_3") (pintype "input"))
      (node (ref "IC1") (pin "4") (pinfunction "RBO_4") (pintype "input"))
      (node (ref "IC1") (pin "5") (pinfunction "RBI_5") (pintype "input"))
      (node (ref "IC10") (pin "5") (pinfunction "VCC_5") (pintype "power_in"))
      (node (ref "IC11") (pin "5") (pinfunction "VCC_5") (pintype "power_in"))
      (node (ref "IC12") (pin "5") (pinfunction "VCC_5") (pintype "power_in"))
      (node (ref "IC13") (pin "5") (pinfunction "VCC_5") (pintype "power_in"))
      (node (ref "IC14") (pin "5") (pinfunction "VCC_5") (pintype "power_in"))
      (node (ref "IC15") (pin "5") (pinfunction "VCC_5") (pintype "power_in"))
      (node (ref "IC16") (pin "5") (pinfunction "VCC_5") (pintype "power_in"))
      (node (ref "IC17") (pin "14") (pinfunction "VCC_14") (pintype "power_in"))
      (node (ref "IC19") (pin "16") (pinfunction "VDD_16") (pintype "power_in"))
      (node (ref "IC2") (pin "16") (pinfunction "VCC_16") (pintype "power_in"))
      (node (ref "IC2") (pin "3") (pinfunction "TEST_3") (pintype "input"))
      (node (ref "IC2") (pin "4") (pinfunction "RBO_4") (pintype "input"))
      (node (ref "IC2") (pin "5") (pinfunction "RBI_5") (pintype "input"))
      (node (ref "IC20") (pin "14") (pinfunction "VCC_14") (pintype "power_in"))
      (node (ref "IC3") (pin "16") (pinfunction "VCC_16") (pintype "power_in"))
      (node (ref "IC3") (pin "3") (pinfunction "TEST_3") (pintype "input"))
      (node (ref "IC3") (pin "4") (pinfunction "RBO_4") (pintype "input"))
      (node (ref "IC3") (pin "5") (pinfunction "RBI_5") (pintype "input"))
      (node (ref "IC4") (pin "16") (pinfunction "VCC_16") (pintype "power_in"))
      (node (ref "IC4") (pin "3") (pinfunction "TEST_3") (pintype "input"))
      (node (ref "IC4") (pin "4") (pinfunction "RBO_4") (pintype "input"))
      (node (ref "IC4") (pin "5") (pinfunction "RBI_5") (pintype "input"))
      (node (ref "IC5") (pin "16") (pinfunction "VCC_16") (pintype "power_in"))
      (node (ref "IC5") (pin "3") (pinfunction "TEST_3") (pintype "input"))
      (node (ref "IC5") (pin "4") (pinfunction "RBO_4") (pintype "input"))
      (node (ref "IC5") (pin "5") (pinfunction "RBI_5") (pintype "input"))
      (node (ref "IC6") (pin "16") (pinfunction "VCC_16") (pintype "power_in"))
      (node (ref "IC6") (pin "3") (pinfunction "TEST_3") (pintype "input"))
      (node (ref "IC6") (pin "4") (pinfunction "RBO_4") (pintype "input"))
      (node (ref "IC6") (pin "5") (pinfunction "RBI_5") (pintype "input"))
      (node (ref "IC7") (pin "16") (pinfunction "VCC_16") (pintype "power_in"))
      (node (ref "IC7") (pin "3") (pinfunction "TEST_3") (pintype "input"))
      (node (ref "IC7") (pin "4") (pinfunction "RBO_4") (pintype "input"))
      (node (ref "IC7") (pin "5") (pinfunction "RBI_5") (pintype "input"))
      (node (ref "IC8") (pin "16") (pinfunction "VCC_16") (pintype "power_in"))
      (node (ref "IC8") (pin "3") (pinfunction "TEST_3") (pintype "input"))
      (node (ref "IC8") (pin "4") (pinfunction "RBO_4") (pintype "input"))
      (node (ref "IC8") (pin "5") (pinfunction "RBI_5") (pintype "input"))
      (node (ref "IC9") (pin "5") (pinfunction "VCC_5") (pintype "power_in"))
      (node (ref "P1") (pin "1") (pinfunction "1_1") (pintype "passive"))
      (node (ref "R0") (pin "1") (pinfunction "1_1") (pintype "passive"))
      (node (ref "R2") (pin "2") (pinfunction "2_2") (pintype "passive"))
      (node (ref "R3") (pin "2") (pinfunction "2_2") (pintype "passive"))
      (node (ref "R4") (pin "2") (pinfunction "2_2") (pintype "passive"))
    )
    (net (code "108") (name "VDD") (class "Default")
      (node (ref "IC18") (pin "14") (pinfunction "VDD_14") (pintype "power_in"))
    )
    (net (code "109") (name "unconnected-(IC19A-P0-Pad9)") (class "Default")
      (node (ref "IC19") (pin "9") (pinfunction "P0_9") (pintype "output"))
    )
    (net (code "110") (name "unconnected-(IC19A-Q4-Pad7)") (class "Default")
      (node (ref "IC19") (pin "7") (pinfunction "Q4_7") (pintype "output"))
    )
    (net (code "111") (name "unconnected-(IC19A-Q5-Pad5)") (class "Default")
      (node (ref "IC19") (pin "5") (pinfunction "Q5_5") (pintype "output"))
    )
    (net (code "112") (name "unconnected-(IC19A-Q6-Pad4)") (class "Default")
      (node (ref "IC19") (pin "4") (pinfunction "Q6_4") (pintype "output"))
    )
    (net (code "113") (name "unconnected-(IC19A-Q7-Pad6)") (class "Default")
      (node (ref "IC19") (pin "6") (pinfunction "Q7_6") (pintype "output"))
    )
    (net (code "114") (name "unconnected-(IC19A-Q8-Pad14)") (class "Default")
      (node (ref "IC19") (pin "14") (pinfunction "Q8_14") (pintype "output"))
    )
    (net (code "115") (name "unconnected-(IC19A-Q9-Pad13)") (class "Default")
      (node (ref "IC19") (pin "13") (pinfunction "Q9_13") (pintype "output"))
    )
    (net (code "116") (name "unconnected-(IC19A-Q10-Pad15)") (class "Default")
      (node (ref "IC19") (pin "15") (pinfunction "Q10_15") (pintype "output"))
    )
    (net (code "117") (name "unconnected-(IC19A-Q12-Pad1)") (class "Default")
      (node (ref "IC19") (pin "1") (pinfunction "Q12_1") (pintype "output"))
    )
    (net (code "118") (name "unconnected-(IC19A-Q13-Pad2)") (class "Default")
      (node (ref "IC19") (pin "2") (pinfunction "Q13_2") (pintype "output"))
    )
    (net (code "119") (name "unconnected-(L1-H-Pad5)") (class "Default")
      (node (ref "L1") (pin "5") (pinfunction "H_5") (pintype "passive"))
    )
    (net (code "120") (name "unconnected-(L2-H-Pad5)") (class "Default")
      (node (ref "L2") (pin "5") (pinfunction "H_5") (pintype "passive"))
    )
    (net (code "121") (name "unconnected-(L3-H-Pad5)") (class "Default")
      (node (ref "L3") (pin "5") (pinfunction "H_5") (pintype "passive"))
    )
    (net (code "122") (name "unconnected-(L4-H-Pad5)") (class "Default")
      (node (ref "L4") (pin "5") (pinfunction "H_5") (pintype "passive"))
    )
    (net (code "123") (name "unconnected-(L5-H-Pad5)") (class "Default")
      (node (ref "L5") (pin "5") (pinfunction "H_5") (pintype "passive"))
    )
    (net (code "124") (name "unconnected-(L6-H-Pad5)") (class "Default")
      (node (ref "L6") (pin "5") (pinfunction "H_5") (pintype "passive"))
    )
    (net (code "125") (name "unconnected-(L7-H-Pad5)") (class "Default")
      (node (ref "L7") (pin "5") (pinfunction "H_5") (pintype "passive"))
    )
    (net (code "126") (name "unconnected-(L8-H-Pad5)") (class "Default")
      (node (ref "L8") (pin "5") (pinfunction "H_5") (pintype "passive"))
    )
  )
)
